# USB-Serial.net
KiCad netlist of a schematic drawn in Altium Designer
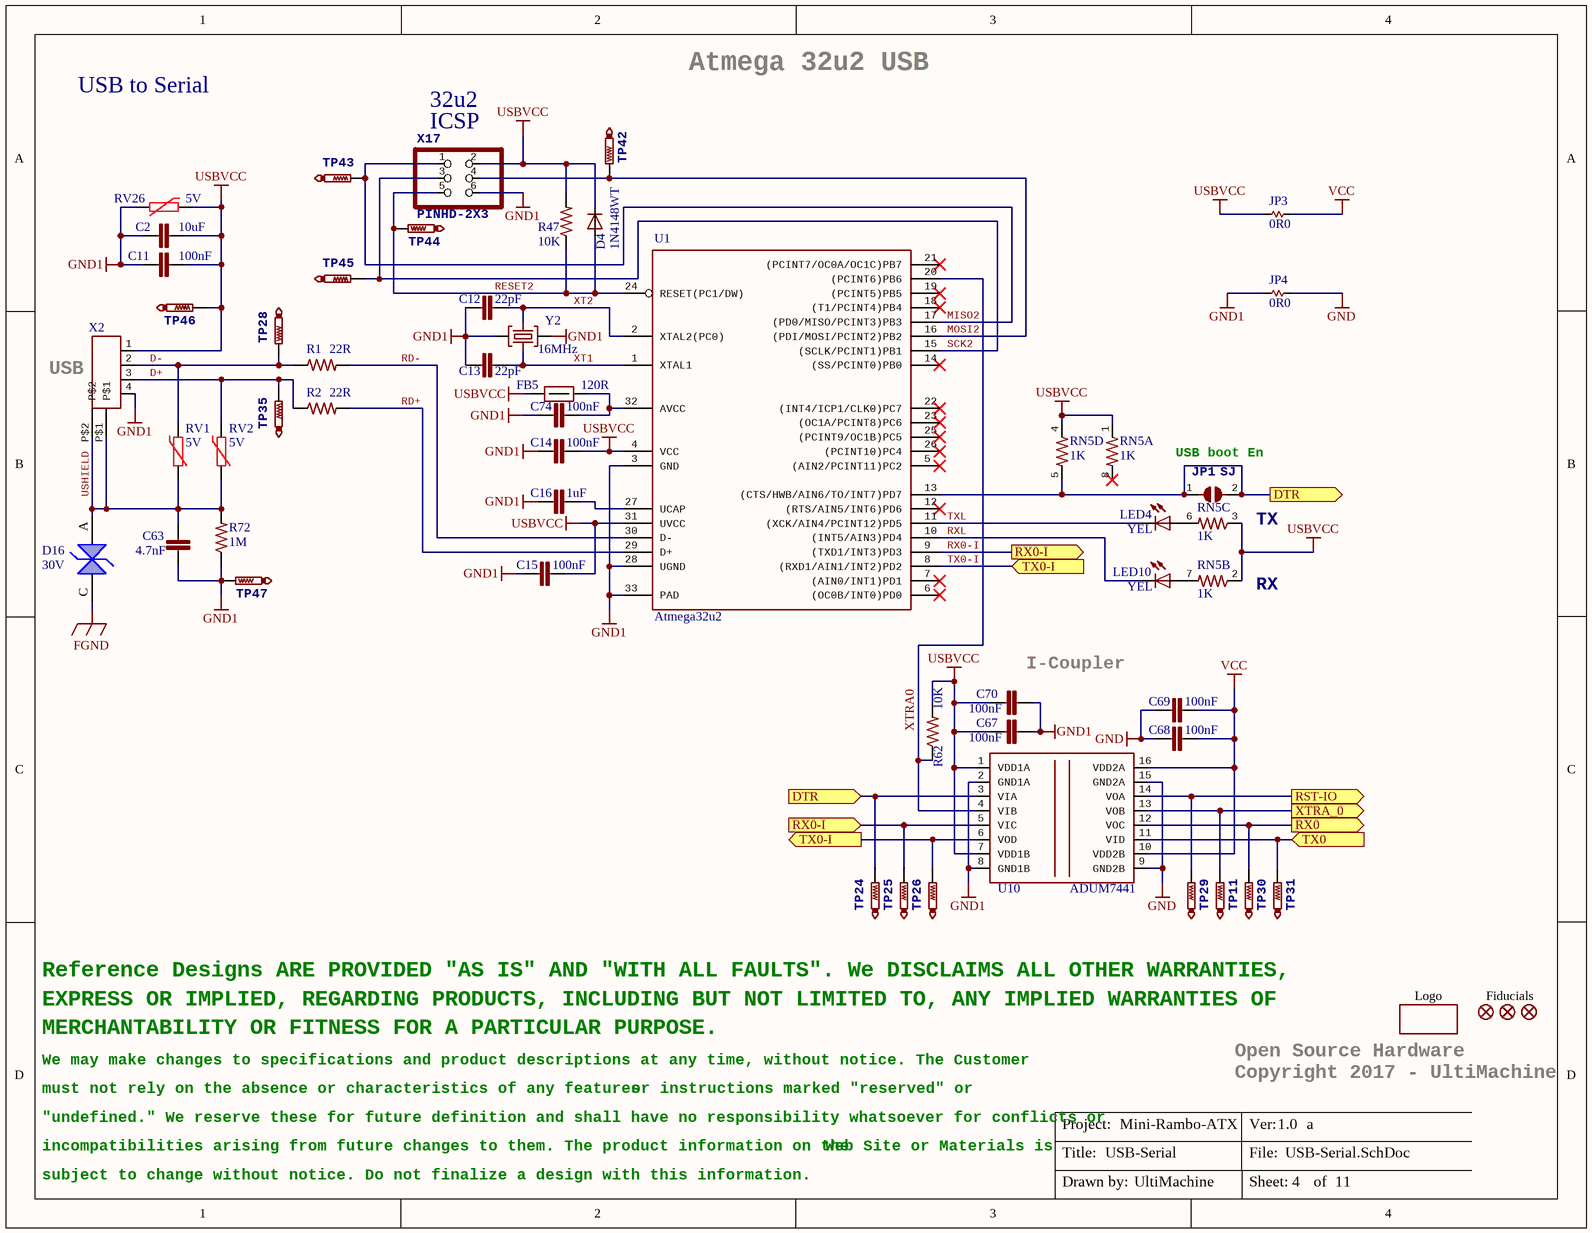
[diagram p0: USB-Serial.SchDoc]

(export (version "E")
  (design (tool "Eeschema 10.0.6"))
  (components
    (comp (ref "C2")
      (value "10uF")
      (footprint "C0805")
      (description "CAP CER 0805 10uF 10V 10% X5R")
      (fields (field (name "MANUFACTURER") "Kemet") (field (name "TOLERANCE") "+/- 10%"))
      (libsource (lib "3Delight") (part "C0805C106K8PACTU"))
    )
    (comp (ref "C11")
      (value "100nF")
      (footprint "C0402")
      (description "CAP CER 0402 100nF 16V 10% X7R")
      (fields (field (name "MANUFACTURER") "Murata") (field (name "TOLERANCE") "+/- 10%"))
      (libsource (lib "3Delight") (part "GRM155R71C104KA88D"))
    )
    (comp (ref "C12")
      (value "22pF")
      (footprint "C0402")
      (description "CAP CER 0402 22pF 50V 5% C0G")
      (fields (field (name "MANUFACTURER") "AVX") (field (name "PART") "22pF 50V"))
      (libsource (lib "3Delight") (part "04025A220JAT2A"))
    )
    (comp (ref "C13")
      (value "22pF")
      (footprint "C0402")
      (description "CAP CER 0402 22pF 50V 5% C0G")
      (fields (field (name "MANUFACTURER") "AVX") (field (name "PART") "22pF 50V"))
      (libsource (lib "3Delight") (part "04025A220JAT2A"))
    )
    (comp (ref "C14")
      (value "100nF")
      (footprint "C0402")
      (description "CAP CER 0402 100nF 16V 10% X7R")
      (fields (field (name "MANUFACTURER") "Murata") (field (name "TOLERANCE") "+/- 10%"))
      (libsource (lib "3Delight") (part "GRM155R71C104KA88D"))
    )
    (comp (ref "C15")
      (value "100nF")
      (footprint "C0402")
      (description "CAP CER 0402 100nF 16V 10% X7R")
      (fields (field (name "MANUFACTURER") "Murata") (field (name "TOLERANCE") "+/- 10%"))
      (libsource (lib "3Delight") (part "GRM155R71C104KA88D"))
    )
    (comp (ref "C16")
      (value "1uF")
      (footprint "C0402")
      (description "CAP CER 0402 1uF 6.3V 10% X5R")
      (fields (field (name "MANUFACTURER") "Murata") (field (name "TOLERANCE") "+/- 10%"))
      (libsource (lib "3Delight") (part "GRM155R60J105KE19D"))
    )
    (comp (ref "C63")
      (value "4.7nF")
      (footprint "C0402")
      (description "CAP CER 0402 4.7nF 25V 10% X7R")
      (fields (field (name "MANUFACTURER") "YAGEO") (field (name "TOLERANCE") "+/- 10%"))
      (libsource (lib "3Delight") (part "CC0402KRX7R8BB472"))
    )
    (comp (ref "C67")
      (value "100nF")
      (footprint "C0402")
      (description "CAP CER 0402 100nF 16V 10% X7R")
      (fields (field (name "MANUFACTURER") "Murata") (field (name "TOLERANCE") "+/- 10%"))
      (libsource (lib "3Delight") (part "GRM155R71C104KA88D"))
    )
    (comp (ref "C68")
      (value "100nF")
      (footprint "C0402")
      (description "CAP CER 0402 100nF 16V 10% X7R")
      (fields (field (name "MANUFACTURER") "Murata") (field (name "TOLERANCE") "+/- 10%"))
      (libsource (lib "") (part "GRM155R71C104KA88D_1"))
    )
    (comp (ref "C69")
      (value "100nF")
      (footprint "C0402")
      (description "CAP CER 0402 100nF 16V 10% X7R")
      (fields (field (name "MANUFACTURER") "Murata") (field (name "TOLERANCE") "+/- 10%"))
      (libsource (lib "3Delight") (part "GRM155R71C104KA88D"))
    )
    (comp (ref "C70")
      (value "100nF")
      (footprint "C0402")
      (description "CAP CER 0402 100nF 16V 10% X7R")
      (fields (field (name "MANUFACTURER") "Murata") (field (name "TOLERANCE") "+/- 10%"))
      (libsource (lib "") (part "GRM155R71C104KA88D_1"))
    )
    (comp (ref "C74")
      (value "100nF")
      (footprint "C0402")
      (description "CAP CER 0402 100nF 16V 10% X7R")
      (fields (field (name "MANUFACTURER") "Murata") (field (name "TOLERANCE") "+/- 10%"))
      (libsource (lib "3Delight") (part "GRM155R71C104KA88D"))
    )
    (comp (ref "D4")
      (value "1N4148WT")
      (footprint "SOD523")
      (description "DIODE SOD523")
      (fields (field (name "MANUFACTURER") "Fairchild") (field (name "TOLERANCE") "NA"))
      (libsource (lib "3Delight") (part "1N4148WT"))
    )
    (comp (ref "D16")
      (value "30V")
      (footprint "SOD323-R")
      (description "DIODE TVS")
      (fields (field (name "MANUFACTURER") "Rohm") (field (name "TOLERANCE") "NA"))
      (libsource (lib "3Delight") (part "RSB39VTE-17"))
    )
    (comp (ref "FB5")
      (value "120R")
      (footprint "FB0603")
      (description "FERRITE BEAD 120 OHM 0603 1LN")
      (fields (field (name "MANUFACTURER") "Samsung") (field (name "PART") "FERRITE 120R 3A 0603"))
      (libsource (lib "3Delight") (part "FERRITE 220R 2.5A 0603"))
    )
    (comp (ref "FID1")
      (value "FIDUCIAL")
      (footprint "FIDUCIAL-1X2")
      (description "Fiducial")
      (libsource (lib "3Delight") (part "FIDUCIAL"))
    )
    (comp (ref "FID2")
      (value "FIDUCIAL")
      (footprint "FIDUCIAL-1X2")
      (description "Fiducial")
      (libsource (lib "3Delight") (part "FIDUCIAL"))
    )
    (comp (ref "FID3")
      (value "FIDUCIAL")
      (footprint "FIDUCIAL-1X2")
      (description "Fiducial")
      (libsource (lib "3Delight") (part "FIDUCIAL"))
    )
    (comp (ref "JP1")
      (value "SJ")
      (footprint "SJ")
      (description "SMD solder jumper")
      (libsource (lib "3Delight") (part "SJ"))
    )
    (comp (ref "JP3")
      (value "0R0")
      (footprint "R0805")
      (description "RES 0.0 OHM 1/8W JUMP 0805 SMD")
      (fields (field (name "MANUFACTURER") "STACKPOLE") (field (name "TOLERANCE") "1%"))
      (libsource (lib "Resistors") (part "0R0 1% 0805"))
    )
    (comp (ref "JP4")
      (value "0R0")
      (footprint "R0805")
      (description "RES 0.0 OHM 1/8W JUMP 0805 SMD")
      (fields (field (name "MANUFACTURER") "STACKPOLE") (field (name "TOLERANCE") "1%"))
      (libsource (lib "Resistors") (part "0R0 1% 0805"))
    )
    (comp (ref "LED4")
      (value "YEL")
      (footprint "LED2012120")
      (description "LED 0805 Yellow")
      (fields (field (name "MANUFACTURER") "Dialight") (field (name "TOLERANCE") "NA"))
      (libsource (lib "3Delight") (part "5988140107F"))
    )
    (comp (ref "LED10")
      (value "YEL")
      (footprint "LED2012120")
      (description "LED 0805 Yellow")
      (fields (field (name "MANUFACTURER") "Dialight") (field (name "TOLERANCE") "NA"))
      (libsource (lib "3Delight") (part "5988140107F"))
    )
    (comp (ref "LOGO1")
      (value "OSHW_LOGO_8MILX0150-NT")
      (footprint "OSHW_8X150_NOTEXT")
      (libsource (lib "3Delight") (part "OSHW_LOGO_8MILX0150-NT"))
    )
    (comp (ref "R1")
      (value "22R")
      (footprint "R0402")
      (description "RES 0402 22r 62.5mW 1%")
      (fields (field (name "MANUFACTURER") "Yageo") (field (name "TOLERANCE") "+/- 1%"))
      (libsource (lib "3Delight") (part "RC0402FR-0722RL"))
    )
    (comp (ref "R2")
      (value "22R")
      (footprint "R0402")
      (description "RES 0402 22r 62.5mW 1%")
      (fields (field (name "MANUFACTURER") "Yageo") (field (name "TOLERANCE") "+/- 1%"))
      (libsource (lib "3Delight") (part "RC0402FR-0722RL"))
    )
    (comp (ref "R47")
      (value "10K")
      (footprint "R0402")
      (description "RES SMD 10K OHM 1% 1/16W 0402")
      (fields (field (name "MANUFACTURER") "Yageo") (field (name "PART") "10k 1% 0402"))
      (libsource (lib "3Delight") (part "RC0402FR-0710KP"))
    )
    (comp (ref "R62")
      (value "10K")
      (footprint "R0402")
      (description "RES SMD 10K OHM 1% 1/16W 0402")
      (fields (field (name "MANUFACTURER") "Yageo") (field (name "PART") "10k 1% 0402"))
      (libsource (lib "3Delight") (part "RC0402FR-0710KP"))
    )
    (comp (ref "R72")
      (value "1M")
      (footprint "R0402")
      (description "RES 0402 1M 100mW 5%")
      (fields (field (name "MANUFACTURER") "Panasonic") (field (name "TOLERANCE") "+/- 1%"))
      (libsource (lib "3Delight") (part "ERJ2GEJ105X"))
    )
    (comp (ref "RN5")
      (value "1K")
      (footprint "CAY16")
      (description "RES ARRAY 4 RES 1K 1206 62.5mW 5%")
      (fields (field (name "MANUFACTURER") "Bourns") (field (name "TOLERANCE") "+/- 5%"))
      (libsource (lib "3Delight") (part "CAY16-102J4LF"))
    )
    (comp (ref "RV1")
      (value "5V")
      (footprint "R0603")
      (description "VAR 0603 5V")
      (fields (field (name "MANUFACTURER") "YAGEO") (field (name "PART") "5VDC"))
      (libsource (lib "3Delight") (part "CG0603MLC-05E"))
    )
    (comp (ref "RV2")
      (value "5V")
      (footprint "R0603")
      (description "VAR 0603 5V")
      (fields (field (name "MANUFACTURER") "YAGEO") (field (name "PART") "5VDC"))
      (libsource (lib "3Delight") (part "CG0603MLC-05E"))
    )
    (comp (ref "RV26")
      (value "5V")
      (footprint "R0603")
      (description "VAR 0603 5V")
      (fields (field (name "MANUFACTURER") "YAGEO") (field (name "PART") "5VDC"))
      (libsource (lib "3Delight") (part "CG0603MLC-05E"))
    )
    (comp (ref "TP11")
      (value "TestPoint")
      (footprint "TP1-27")
      (description "Test Point")
      (libsource (lib "3Delight") (part "TestPoint"))
    )
    (comp (ref "TP24")
      (value "TestPoint")
      (footprint "TP1-27")
      (description "Test Point")
      (libsource (lib "3Delight") (part "TestPoint"))
    )
    (comp (ref "TP25")
      (value "TestPoint")
      (footprint "TP1-27")
      (description "Test Point")
      (libsource (lib "3Delight") (part "TestPoint"))
    )
    (comp (ref "TP26")
      (value "TestPoint")
      (footprint "TP1-27")
      (description "Test Point")
      (libsource (lib "3Delight") (part "TestPoint"))
    )
    (comp (ref "TP28")
      (value "TestPoint")
      (footprint "TP1-27")
      (description "Test Point")
      (libsource (lib "") (part "TestPoint_1"))
    )
    (comp (ref "TP29")
      (value "TestPoint")
      (footprint "TP1-27")
      (description "Test Point")
      (libsource (lib "3Delight") (part "TestPoint"))
    )
    (comp (ref "TP30")
      (value "TestPoint")
      (footprint "TP1-27")
      (description "Test Point")
      (libsource (lib "3Delight") (part "TestPoint"))
    )
    (comp (ref "TP31")
      (value "TestPoint")
      (footprint "TP1-27")
      (description "Test Point")
      (libsource (lib "3Delight") (part "TestPoint"))
    )
    (comp (ref "TP35")
      (value "TestPoint")
      (footprint "TP1-27")
      (description "Test Point")
      (libsource (lib "3Delight") (part "TestPoint"))
    )
    (comp (ref "TP42")
      (value "TestPoint")
      (footprint "TP1-27")
      (description "Test Point")
      (libsource (lib "") (part "TestPoint_1"))
    )
    (comp (ref "TP43")
      (value "TestPoint")
      (footprint "TP1-27")
      (description "Test Point")
      (libsource (lib "") (part "TestPoint_2"))
    )
    (comp (ref "TP44")
      (value "TestPoint")
      (footprint "TP1-27")
      (description "Test Point")
      (libsource (lib "") (part "TestPoint_3"))
    )
    (comp (ref "TP45")
      (value "TestPoint")
      (footprint "TP1-27")
      (description "Test Point")
      (libsource (lib "") (part "TestPoint_2"))
    )
    (comp (ref "TP46")
      (value "TestPoint")
      (footprint "TP1-27")
      (description "Test Point")
      (libsource (lib "") (part "TestPoint_2"))
    )
    (comp (ref "TP47")
      (value "TestPoint")
      (footprint "TP1-27")
      (description "Test Point")
      (libsource (lib "") (part "TestPoint_3"))
    )
    (comp (ref "U1")
      (value "Atmega32u2")
      (footprint "QFN32_DualSolderMask")
      (fields
        (field (name "MANUFACTURER") "Microchip")
        (field (name "PART") "ATMEGA32U2")
        (field (name "TOLERANCE") "NA")
      )
      (libsource (lib "ICs-uC") (part "ATMEGA32U2-DualSolderMask"))
    )
    (comp (ref "U10")
      (value "ADUM7441")
      (footprint "QSOP16")
      (description "4ch iCoupler")
      (fields (field (name "MANUFACTURER") "Analog Devices") (field (name "PART") "ADUM7441ARQZ"))
      (libsource (lib "3Delight") (part "ADUM7441"))
    )
    (comp (ref "X2")
      (value "USB-B")
      (footprint "PN61729")
      (description "USB connector B PTH")
      (fields (field (name "MANUFACTURER") "FCI") (field (name "TOLERANCE") "NA"))
      (libsource (lib "3Delight") (part "USB-B"))
    )
    (comp (ref "X17")
      (value "PINHD-2X3")
      (footprint "2X03")
      (description "CONN HEADER VERT 6POS GOLD")
      (fields (field (name "MANUFACTURER") "MultiComp") (field (name "PART") "6PIN"))
      (libsource (lib "Connectors") (part "PINHD-2X3"))
    )
    (comp (ref "Y2")
      (value "16MHz")
      (footprint "CRYS320250")
      (description "Crystal 16mHz 10ppm 10pF")
      (fields (field (name "MANUFACTURER") "TXC") (field (name "TOLERANCE") "10ppm"))
      (libsource (lib "3Delight") (part "7M-16.000MEEQ-T"))
    )
  )
  (nets
    (net (code "1") (name "/D+") (class "Default")
      (node (ref "R2") (pin "1") (pinfunction "1_1") (pintype "passive"))
      (node (ref "RV2") (pin "2") (pinfunction "2_2") (pintype "passive"))
      (node (ref "TP35") (pin "TP") (pinfunction "TP_TP") (pintype "passive"))
      (node (ref "X2") (pin "3") (pinfunction "3_3") (pintype "passive"))
    )
    (net (code "2") (name "/D-") (class "Default")
      (node (ref "R1") (pin "1") (pinfunction "1_1") (pintype "passive"))
      (node (ref "RV1") (pin "2") (pinfunction "2_2") (pintype "passive"))
      (node (ref "TP28") (pin "TP") (pinfunction "TP_TP") (pintype "passive"))
      (node (ref "X2") (pin "2") (pinfunction "2_2") (pintype "passive"))
    )
    (net (code "3") (name "/DTR") (class "Default")
      (node (ref "JP1") (pin "1") (pinfunction "1_1") (pintype "passive"))
      (node (ref "JP1") (pin "2") (pinfunction "2_2") (pintype "passive"))
      (node (ref "RN5") (pin "5") (pinfunction "2_5") (pintype "passive"))
      (node (ref "TP24") (pin "TP") (pinfunction "TP_TP") (pintype "passive"))
      (node (ref "U1") (pin "13") (pinfunction "(CTS/HWB/AIN6/TO/INT7)PD7_13") (pintype "passive"))
      (node (ref "U10") (pin "3") (pinfunction "VIA_3") (pintype "passive"))
    )
    (net (code "4") (name "/MISO2") (class "Default")
      (node (ref "TP43") (pin "TP") (pinfunction "TP_TP") (pintype "passive"))
      (node (ref "U1") (pin "17") (pinfunction "(PD0/MISO/PCINT3)PB3_17") (pintype "passive"))
      (node (ref "X17") (pin "1") (pinfunction "1_1") (pintype "passive"))
    )
    (net (code "5") (name "/MOSI2") (class "Default")
      (node (ref "TP42") (pin "TP") (pinfunction "TP_TP") (pintype "passive"))
      (node (ref "U1") (pin "16") (pinfunction "(PDI/MOSI/PCINT2)PB2_16") (pintype "passive"))
      (node (ref "X17") (pin "4") (pinfunction "4_4") (pintype "passive"))
    )
    (net (code "6") (name "/RD+") (class "Default")
      (node (ref "R2") (pin "2") (pinfunction "2_2") (pintype "passive"))
      (node (ref "U1") (pin "29") (pinfunction "D+_29") (pintype "passive"))
    )
    (net (code "7") (name "/RD-") (class "Default")
      (node (ref "R1") (pin "2") (pinfunction "2_2") (pintype "passive"))
      (node (ref "U1") (pin "30") (pinfunction "D-_30") (pintype "passive"))
    )
    (net (code "8") (name "/RESET2") (class "Default")
      (node (ref "D4") (pin "A") (pinfunction "A_A") (pintype "passive"))
      (node (ref "R47") (pin "1") (pinfunction "1_1") (pintype "passive"))
      (node (ref "TP44") (pin "TP") (pinfunction "TP_TP") (pintype "passive"))
      (node (ref "U1") (pin "24") (pinfunction "RESET(PC1/DW)_24") (pintype "passive"))
      (node (ref "X17") (pin "5") (pinfunction "5_5") (pintype "passive"))
    )
    (net (code "9") (name "/RST-IO") (class "Default")
      (node (ref "TP29") (pin "TP") (pinfunction "TP_TP") (pintype "passive"))
      (node (ref "U10") (pin "14") (pinfunction "VOA_14") (pintype "passive"))
    )
    (net (code "10") (name "/RX0") (class "Default")
      (node (ref "TP30") (pin "TP") (pinfunction "TP_TP") (pintype "passive"))
      (node (ref "U10") (pin "12") (pinfunction "VOC_12") (pintype "passive"))
    )
    (net (code "11") (name "/RX0-I") (class "Default")
      (node (ref "TP25") (pin "TP") (pinfunction "TP_TP") (pintype "passive"))
      (node (ref "U1") (pin "9") (pinfunction "(TXD1/INT3)PD3_9") (pintype "passive"))
      (node (ref "U10") (pin "5") (pinfunction "VIC_5") (pintype "passive"))
    )
    (net (code "12") (name "/RXL") (class "Default")
      (node (ref "LED10") (pin "C") (pinfunction "C_C") (pintype "passive"))
      (node (ref "U1") (pin "10") (pinfunction "(INT5/AIN3)PD4_10") (pintype "passive"))
    )
    (net (code "13") (name "/SCK2") (class "Default")
      (node (ref "TP45") (pin "TP") (pinfunction "TP_TP") (pintype "passive"))
      (node (ref "U1") (pin "15") (pinfunction "(SCLK/PCINT1)PB1_15") (pintype "passive"))
      (node (ref "X17") (pin "3") (pinfunction "3_3") (pintype "passive"))
    )
    (net (code "14") (name "/TX0") (class "Default")
      (node (ref "TP31") (pin "TP") (pinfunction "TP_TP") (pintype "passive"))
      (node (ref "U10") (pin "11") (pinfunction "VID_11") (pintype "passive"))
    )
    (net (code "15") (name "/TX0-I") (class "Default")
      (node (ref "TP26") (pin "TP") (pinfunction "TP_TP") (pintype "passive"))
      (node (ref "U1") (pin "8") (pinfunction "(RXD1/AIN1/INT2)PD2_8") (pintype "passive"))
      (node (ref "U10") (pin "6") (pinfunction "VOD_6") (pintype "passive"))
    )
    (net (code "16") (name "/TXL") (class "Default")
      (node (ref "LED4") (pin "C") (pinfunction "C_C") (pintype "passive"))
      (node (ref "U1") (pin "11") (pinfunction "(XCK/AIN4/PCINT12)PD5_11") (pintype "passive"))
    )
    (net (code "17") (name "/USHIELD") (class "Default")
      (node (ref "C63") (pin "1") (pinfunction "1_1") (pintype "passive"))
      (node (ref "D16") (pin "A") (pinfunction "A_A") (pintype "power_in"))
      (node (ref "R72") (pin "2") (pinfunction "2_2") (pintype "passive"))
      (node (ref "RV1") (pin "1") (pinfunction "1_1") (pintype "passive"))
      (node (ref "RV2") (pin "1") (pinfunction "1_1") (pintype "passive"))
      (node (ref "X2") (pin "P$1") (pinfunction "P$1_P$1") (pintype "passive"))
      (node (ref "X2") (pin "P$2") (pinfunction "P$2_P$2") (pintype "passive"))
    )
    (net (code "18") (name "/XT1") (class "Default")
      (node (ref "C13") (pin "1") (pinfunction "1_1") (pintype "passive"))
      (node (ref "U1") (pin "1") (pinfunction "XTAL1_1") (pintype "passive"))
      (node (ref "Y2") (pin "1") (pinfunction "C1_1") (pintype "passive"))
    )
    (net (code "19") (name "/XT2") (class "Default")
      (node (ref "C12") (pin "1") (pinfunction "1_1") (pintype "passive"))
      (node (ref "U1") (pin "2") (pinfunction "XTAL2(PC0)_2") (pintype "passive"))
      (node (ref "Y2") (pin "3") (pinfunction "C2_3") (pintype "passive"))
    )
    (net (code "20") (name "/XTRA0") (class "Default")
      (node (ref "R62") (pin "1") (pinfunction "1_1") (pintype "passive"))
      (node (ref "U1") (pin "20") (pinfunction "(PCINT6)PB6_20") (pintype "passive"))
      (node (ref "U10") (pin "4") (pinfunction "VIB_4") (pintype "passive"))
    )
    (net (code "21") (name "/XTRA_0") (class "Default")
      (node (ref "TP11") (pin "TP") (pinfunction "TP_TP") (pintype "passive"))
      (node (ref "U10") (pin "13") (pinfunction "VOB_13") (pintype "passive"))
    )
    (net (code "22") (name "FGND") (class "Default")
      (node (ref "D16") (pin "C") (pinfunction "C_C") (pintype "power_in"))
    )
    (net (code "23") (name "GND") (class "Default")
      (node (ref "C68") (pin "1") (pinfunction "1_1") (pintype "passive"))
      (node (ref "C69") (pin "2") (pinfunction "2_2") (pintype "passive"))
      (node (ref "JP4") (pin "2") (pinfunction "2_2") (pintype "passive"))
      (node (ref "U10") (pin "15") (pinfunction "GND2A_15") (pintype "passive"))
      (node (ref "U10") (pin "9") (pinfunction "GND2B_9") (pintype "passive"))
    )
    (net (code "24") (name "GND1") (class "Default")
      (node (ref "C11") (pin "2") (pinfunction "2_2") (pintype "passive"))
      (node (ref "C12") (pin "2") (pinfunction "2_2") (pintype "passive"))
      (node (ref "C13") (pin "2") (pinfunction "2_2") (pintype "passive"))
      (node (ref "C14") (pin "2") (pinfunction "2_2") (pintype "passive"))
      (node (ref "C15") (pin "2") (pinfunction "2_2") (pintype "passive"))
      (node (ref "C16") (pin "2") (pinfunction "2_2") (pintype "passive"))
      (node (ref "C2") (pin "1") (pinfunction "1_1") (pintype "passive"))
      (node (ref "C63") (pin "2") (pinfunction "2_2") (pintype "passive"))
      (node (ref "C67") (pin "1") (pinfunction "1_1") (pintype "passive"))
      (node (ref "C70") (pin "2") (pinfunction "2_2") (pintype "passive"))
      (node (ref "C74") (pin "2") (pinfunction "2_2") (pintype "passive"))
      (node (ref "JP4") (pin "1") (pinfunction "1_1") (pintype "passive"))
      (node (ref "R72") (pin "1") (pinfunction "1_1") (pintype "passive"))
      (node (ref "RV26") (pin "1") (pinfunction "1_1") (pintype "passive"))
      (node (ref "TP47") (pin "TP") (pinfunction "TP_TP") (pintype "passive"))
      (node (ref "U1") (pin "28") (pinfunction "UGND_28") (pintype "power_in"))
      (node (ref "U1") (pin "3") (pinfunction "GND_3") (pintype "power_in"))
      (node (ref "U1") (pin "33") (pinfunction "PAD_33") (pintype "power_in"))
      (node (ref "U10") (pin "2") (pinfunction "GND1A_2") (pintype "passive"))
      (node (ref "U10") (pin "8") (pinfunction "GND1B_8") (pintype "passive"))
      (node (ref "X17") (pin "6") (pinfunction "6_6") (pintype "passive"))
      (node (ref "X2") (pin "4") (pinfunction "4_4") (pintype "passive"))
      (node (ref "Y2") (pin "2") (pinfunction "GND_2") (pintype "passive"))
      (node (ref "Y2") (pin "4") (pinfunction "GND_4") (pintype "passive"))
    )
    (net (code "25") (name "Net-(RN5B-2)") (class "Default")
      (node (ref "LED10") (pin "A") (pinfunction "A_A") (pintype "passive"))
      (node (ref "RN5") (pin "7") (pinfunction "2_7") (pintype "passive"))
    )
    (net (code "26") (name "Net-(RN5C-2)") (class "Default")
      (node (ref "LED4") (pin "A") (pinfunction "A_A") (pintype "passive"))
      (node (ref "RN5") (pin "6") (pinfunction "2_6") (pintype "passive"))
    )
    (net (code "27") (name "Net-(U1-AVCC)") (class "Default")
      (node (ref "C74") (pin "1") (pinfunction "1_1") (pintype "passive"))
      (node (ref "FB5") (pin "2") (pinfunction "2_2") (pintype "passive"))
      (node (ref "U1") (pin "32") (pinfunction "AVCC_32") (pintype "power_in"))
    )
    (net (code "28") (name "Net-(U1-UCAP)") (class "Default")
      (node (ref "C16") (pin "1") (pinfunction "1_1") (pintype "passive"))
      (node (ref "U1") (pin "27") (pinfunction "UCAP_27") (pintype "passive"))
    )
    (net (code "29") (name "USBVCC") (class "Default")
      (node (ref "C11") (pin "1") (pinfunction "1_1") (pintype "passive"))
      (node (ref "C14") (pin "1") (pinfunction "1_1") (pintype "passive"))
      (node (ref "C15") (pin "1") (pinfunction "1_1") (pintype "passive"))
      (node (ref "C2") (pin "2") (pinfunction "2_2") (pintype "passive"))
      (node (ref "C67") (pin "2") (pinfunction "2_2") (pintype "passive"))
      (node (ref "C70") (pin "1") (pinfunction "1_1") (pintype "passive"))
      (node (ref "D4") (pin "C") (pinfunction "C_C") (pintype "passive"))
      (node (ref "FB5") (pin "1") (pinfunction "1_1") (pintype "passive"))
      (node (ref "JP3") (pin "1") (pinfunction "1_1") (pintype "passive"))
      (node (ref "R47") (pin "2") (pinfunction "2_2") (pintype "passive"))
      (node (ref "R62") (pin "2") (pinfunction "2_2") (pintype "passive"))
      (node (ref "RN5") (pin "1") (pinfunction "1_1") (pintype "passive"))
      (node (ref "RN5") (pin "2") (pinfunction "1_2") (pintype "passive"))
      (node (ref "RN5") (pin "3") (pinfunction "1_3") (pintype "passive"))
      (node (ref "RN5") (pin "4") (pinfunction "1_4") (pintype "passive"))
      (node (ref "RV26") (pin "2") (pinfunction "2_2") (pintype "passive"))
      (node (ref "TP46") (pin "TP") (pinfunction "TP_TP") (pintype "passive"))
      (node (ref "U1") (pin "31") (pinfunction "UVCC_31") (pintype "power_in"))
      (node (ref "U1") (pin "4") (pinfunction "VCC_4") (pintype "power_in"))
      (node (ref "U10") (pin "1") (pinfunction "VDD1A_1") (pintype "passive"))
      (node (ref "U10") (pin "7") (pinfunction "VDD1B_7") (pintype "passive"))
      (node (ref "X17") (pin "2") (pinfunction "2_2") (pintype "passive"))
      (node (ref "X2") (pin "1") (pinfunction "1_1") (pintype "passive"))
    )
    (net (code "30") (name "VCC") (class "Default")
      (node (ref "C68") (pin "2") (pinfunction "2_2") (pintype "passive"))
      (node (ref "C69") (pin "1") (pinfunction "1_1") (pintype "passive"))
      (node (ref "JP3") (pin "2") (pinfunction "2_2") (pintype "passive"))
      (node (ref "U10") (pin "10") (pinfunction "VDD2B_10") (pintype "passive"))
      (node (ref "U10") (pin "16") (pinfunction "VDD2A_16") (pintype "passive"))
    )
    (net (code "31") (name "unconnected-(RN5A-2-Pad8)") (class "Default")
      (node (ref "RN5") (pin "8") (pinfunction "2_8") (pintype "passive+no_connect"))
    )
    (net (code "32") (name "unconnected-(U1-(AIN0{slash}INT1)PD1-Pad7)") (class "Default")
      (node (ref "U1") (pin "7") (pinfunction "(AIN0/INT1)PD1_7") (pintype "passive+no_connect"))
    )
    (net (code "33") (name "unconnected-(U1-(AIN2{slash}PCINT11)PC2-Pad5)") (class "Default")
      (node (ref "U1") (pin "5") (pinfunction "(AIN2/PCINT11)PC2_5") (pintype "passive+no_connect"))
    )
    (net (code "34") (name "unconnected-(U1-(INT4{slash}ICP1{slash}CLK0)PC7-Pad22)") (class "Default")
      (node (ref "U1") (pin "22") (pinfunction "(INT4/ICP1/CLK0)PC7_22") (pintype "passive+no_connect"))
    )
    (net (code "35") (name "unconnected-(U1-(OC0B{slash}INT0)PD0-Pad6)") (class "Default")
      (node (ref "U1") (pin "6") (pinfunction "(OC0B/INT0)PD0_6") (pintype "passive+no_connect"))
    )
    (net (code "36") (name "unconnected-(U1-(OC1A{slash}PCINT8)PC6-Pad23)") (class "Default")
      (node (ref "U1") (pin "23") (pinfunction "(OC1A/PCINT8)PC6_23") (pintype "passive+no_connect"))
    )
    (net (code "37") (name "unconnected-(U1-(PCINT5)PB5-Pad19)") (class "Default")
      (node (ref "U1") (pin "19") (pinfunction "(PCINT5)PB5_19") (pintype "passive+no_connect"))
    )
    (net (code "38") (name "unconnected-(U1-(PCINT7{slash}OC0A{slash}OC1C)PB7-Pad21)") (class "Default")
      (node (ref "U1") (pin "21") (pinfunction "(PCINT7/OC0A/OC1C)PB7_21") (pintype "passive+no_connect"))
    )
    (net (code "39") (name "unconnected-(U1-(PCINT9{slash}OC1B)PC5-Pad25)") (class "Default")
      (node (ref "U1") (pin "25") (pinfunction "(PCINT9/OC1B)PC5_25") (pintype "passive+no_connect"))
    )
    (net (code "40") (name "unconnected-(U1-(PCINT10)PC4-Pad26)") (class "Default")
      (node (ref "U1") (pin "26") (pinfunction "(PCINT10)PC4_26") (pintype "passive+no_connect"))
    )
    (net (code "41") (name "unconnected-(U1-(RTS{slash}AIN5{slash}INT6)PD6-Pad12)") (class "Default")
      (node (ref "U1") (pin "12") (pinfunction "(RTS/AIN5/INT6)PD6_12") (pintype "passive+no_connect"))
    )
    (net (code "42") (name "unconnected-(U1-(SS{slash}PCINT0)PB0-Pad14)") (class "Default")
      (node (ref "U1") (pin "14") (pinfunction "(SS/PCINT0)PB0_14") (pintype "passive+no_connect"))
    )
    (net (code "43") (name "unconnected-(U1-(T1{slash}PCINT4)PB4-Pad18)") (class "Default")
      (node (ref "U1") (pin "18") (pinfunction "(T1/PCINT4)PB4_18") (pintype "passive+no_connect"))
    )
  )
)
